# NIRGM_V3_E7.net
KiCad netlist of a schematic drawn in EAGLE
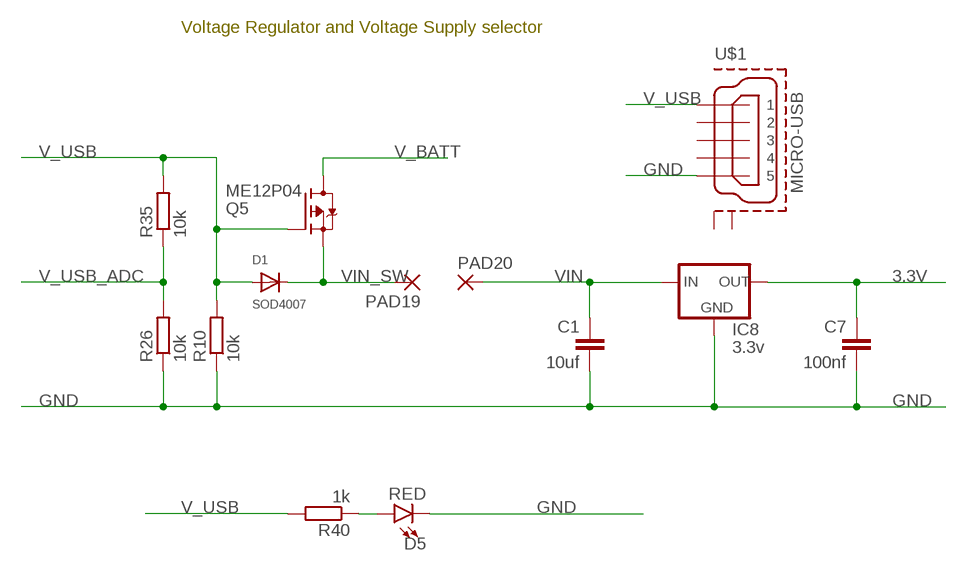
[diagram p0: schematic, sheet 1]
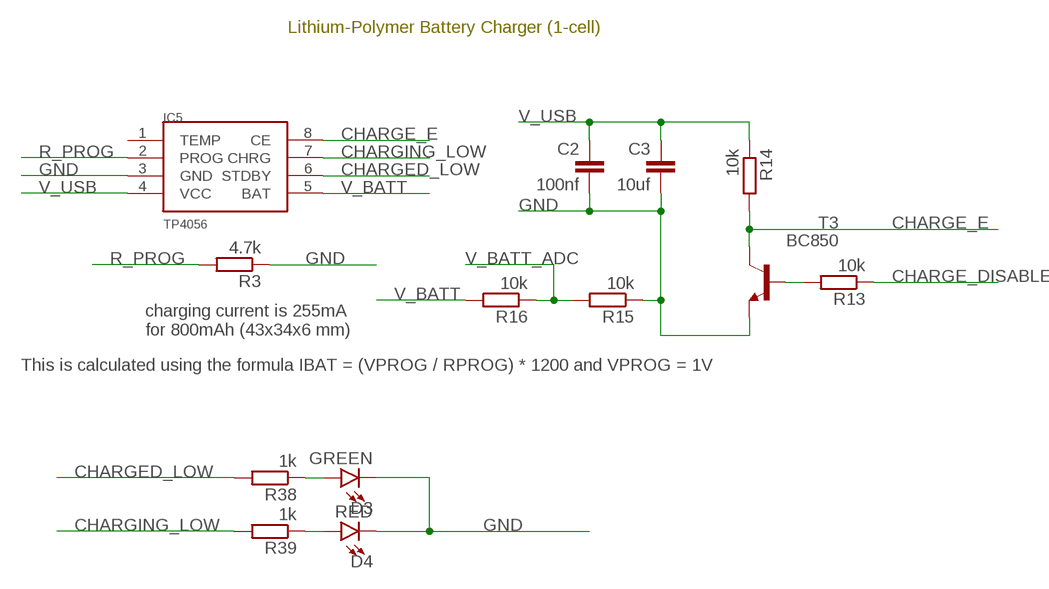
[diagram p1: schematic, sheet 2]
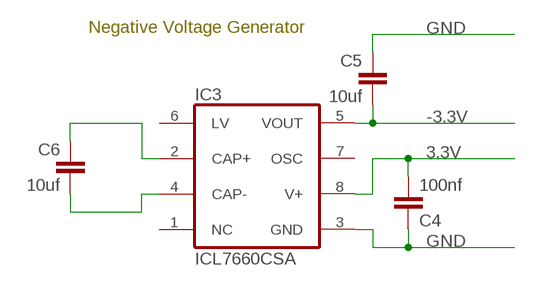
[diagram p2: schematic, sheet 3]
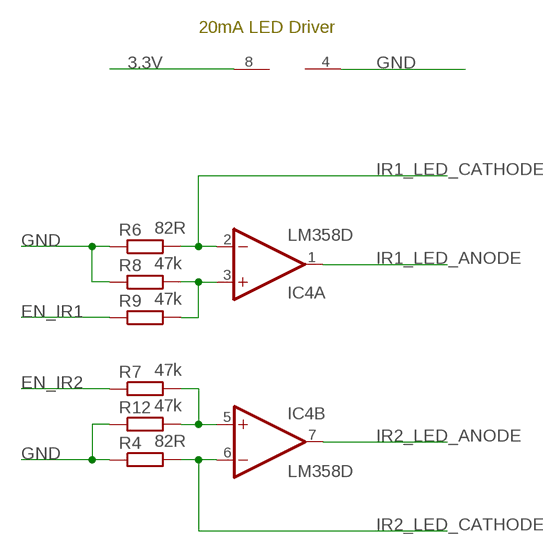
[diagram p3: schematic, sheet 4]
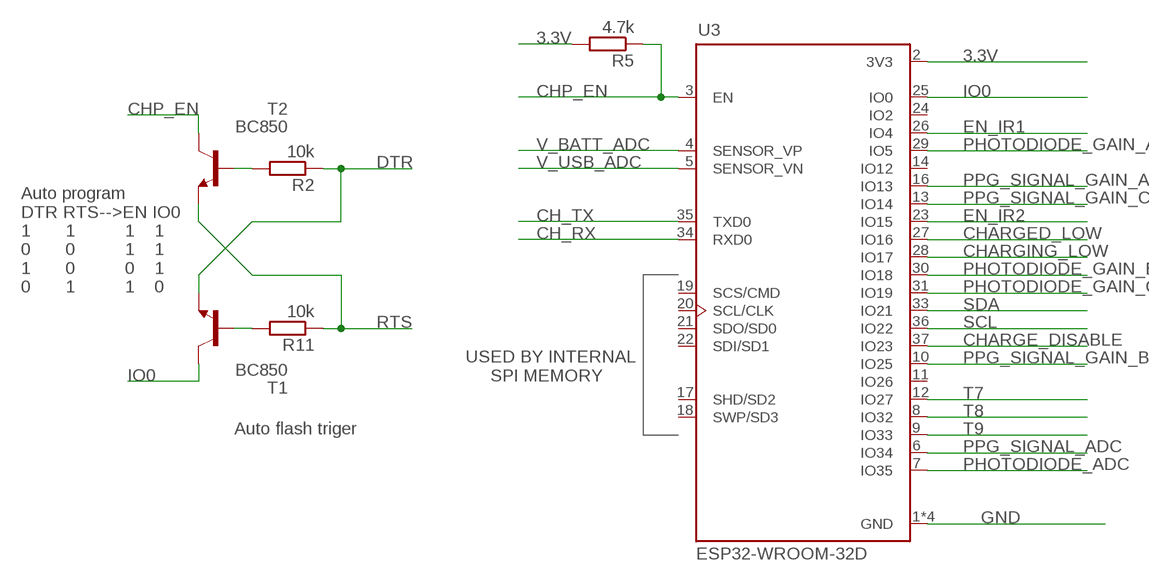
[diagram p4: schematic, sheet 5]
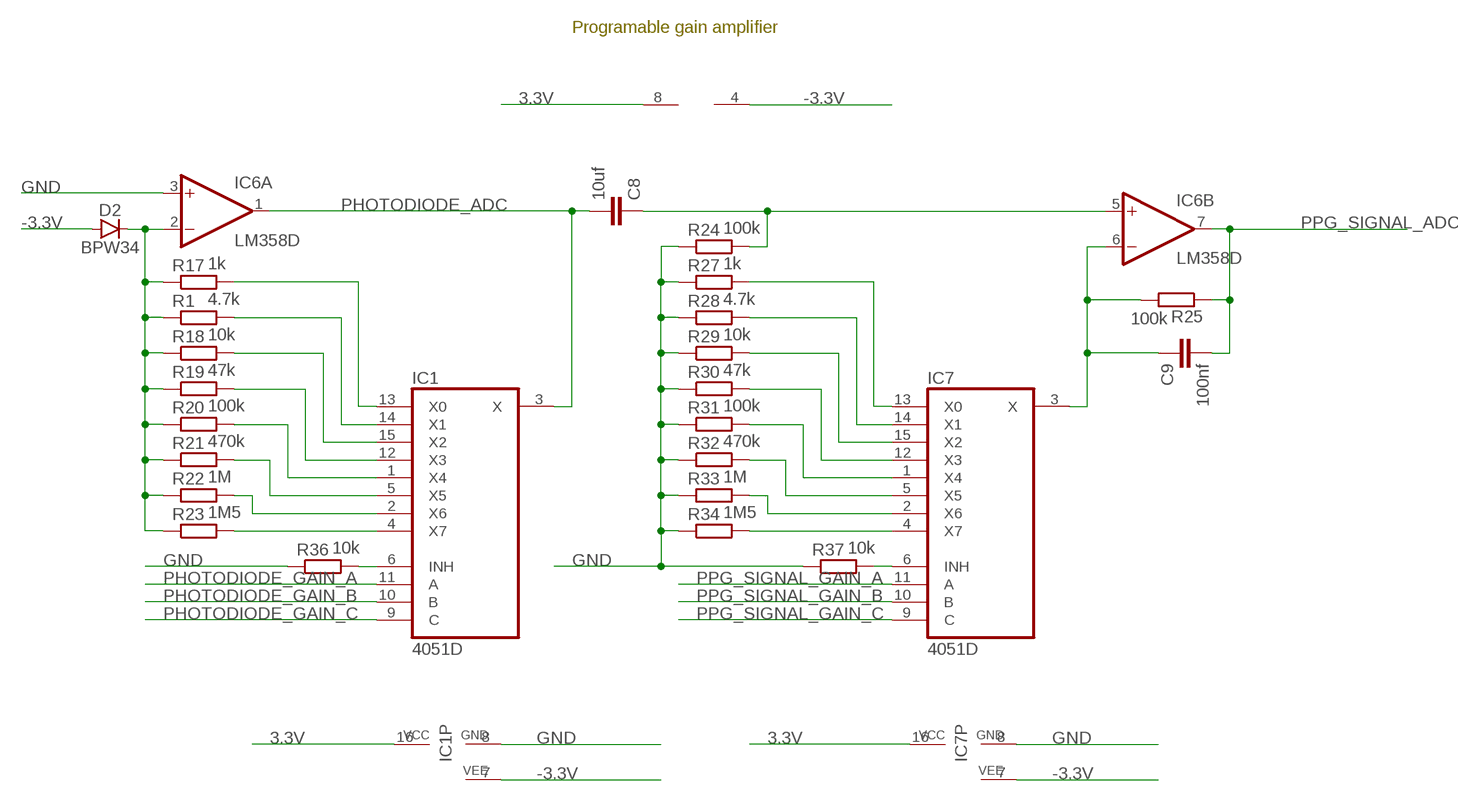
[diagram p5: schematic, sheet 6]
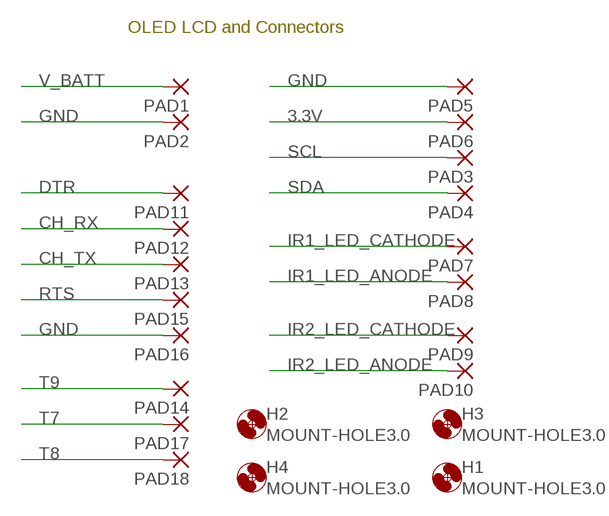
[diagram p6: schematic, sheet 7]

(export (version "E")
  (design (tool "Eeschema 10.0.6"))
  (components
    (comp (ref "IC4")
      (value "LM358D")
      (footprint "eagle-import:SO08")
      (libsource (lib "eagle-import") (part "LM358D"))
    )
    (comp (ref "R4")
      (value "82R")
      (footprint "eagle-import:R1206")
      (libsource (lib "eagle-import") (part "R-EU_R1206"))
    )
    (comp (ref "R6")
      (value "82R")
      (footprint "eagle-import:R1206")
      (libsource (lib "eagle-import") (part "R-EU_R1206"))
    )
    (comp (ref "R7")
      (value "47k")
      (footprint "eagle-import:R1206")
      (libsource (lib "eagle-import") (part "R-EU_R1206"))
    )
    (comp (ref "R8")
      (value "47k")
      (footprint "eagle-import:R1206")
      (libsource (lib "eagle-import") (part "R-EU_R1206"))
    )
    (comp (ref "R9")
      (value "47k")
      (footprint "eagle-import:R1206")
      (libsource (lib "eagle-import") (part "R-EU_R1206"))
    )
    (comp (ref "R12")
      (value "47k")
      (footprint "eagle-import:R1206")
      (libsource (lib "eagle-import") (part "R-EU_R1206"))
    )
    (comp (ref "C2")
      (value "100nf")
      (footprint "eagle-import:C1206K")
      (libsource (lib "eagle-import") (part "C-EUC1206K"))
    )
    (comp (ref "C3")
      (value "10uf")
      (footprint "eagle-import:C1206K")
      (libsource (lib "eagle-import") (part "C-EUC1206K"))
    )
    (comp (ref "D3")
      (value "GREEN")
      (footprint "eagle-import:LED-1206")
      (libsource (lib "eagle-import") (part "LED-GREEN1206"))
    )
    (comp (ref "D4")
      (value "RED")
      (footprint "eagle-import:LED-1206")
      (libsource (lib "eagle-import") (part "LED-GREEN1206"))
    )
    (comp (ref "IC5")
      (value "TP4056")
      (footprint "eagle-import:SOP-8")
      (libsource (lib "eagle-import") (part "TP4056"))
    )
    (comp (ref "R3")
      (value "4.7k")
      (footprint "eagle-import:R1206")
      (libsource (lib "eagle-import") (part "R-EU_R1206"))
    )
    (comp (ref "R13")
      (value "10k")
      (footprint "eagle-import:R1206")
      (libsource (lib "eagle-import") (part "R-EU_R1206"))
    )
    (comp (ref "R14")
      (value "10k")
      (footprint "eagle-import:R1206")
      (libsource (lib "eagle-import") (part "R-EU_R1206"))
    )
    (comp (ref "R15")
      (value "10k")
      (footprint "eagle-import:R1206")
      (libsource (lib "eagle-import") (part "R-EU_R1206"))
    )
    (comp (ref "R16")
      (value "10k")
      (footprint "eagle-import:R1206")
      (libsource (lib "eagle-import") (part "R-EU_R1206"))
    )
    (comp (ref "R38")
      (value "1k")
      (footprint "eagle-import:R1206")
      (libsource (lib "eagle-import") (part "R-EU_R1206"))
    )
    (comp (ref "R39")
      (value "1k")
      (footprint "eagle-import:R1206")
      (libsource (lib "eagle-import") (part "R-EU_R1206"))
    )
    (comp (ref "T3")
      (value "BC850")
      (footprint "eagle-import:SOT23")
      (libsource (lib "eagle-import") (part "BC850"))
    )
    (comp (ref "C8")
      (value "10uf")
      (footprint "eagle-import:C1206K")
      (libsource (lib "eagle-import") (part "C-EUC1206K"))
    )
    (comp (ref "C9")
      (value "100nf")
      (footprint "eagle-import:C1206K")
      (libsource (lib "eagle-import") (part "C-EUC1206K"))
    )
    (comp (ref "D2")
      (value "BPW34")
      (footprint "eagle-import:BPW34")
      (libsource (lib "eagle-import") (part "BPW34"))
    )
    (comp (ref "IC1")
      (value "4051D")
      (footprint "eagle-import:SO16")
      (libsource (lib "eagle-import") (part "4051D"))
    )
    (comp (ref "IC6")
      (value "LM358D")
      (footprint "eagle-import:SO08")
      (libsource (lib "eagle-import") (part "linear@1_LM358D"))
    )
    (comp (ref "IC7")
      (value "4051D")
      (footprint "eagle-import:SO16")
      (libsource (lib "eagle-import") (part "4051D"))
    )
    (comp (ref "R1")
      (value "4.7k")
      (footprint "eagle-import:R1206")
      (libsource (lib "eagle-import") (part "R-EU_R1206"))
    )
    (comp (ref "R17")
      (value "1k")
      (footprint "eagle-import:R1206")
      (libsource (lib "eagle-import") (part "R-EU_R1206"))
    )
    (comp (ref "R18")
      (value "10k")
      (footprint "eagle-import:R1206")
      (libsource (lib "eagle-import") (part "R-EU_R1206"))
    )
    (comp (ref "R19")
      (value "47k")
      (footprint "eagle-import:R1206")
      (libsource (lib "eagle-import") (part "R-EU_R1206"))
    )
    (comp (ref "R20")
      (value "100k")
      (footprint "eagle-import:R1206")
      (libsource (lib "eagle-import") (part "R-EU_R1206"))
    )
    (comp (ref "R21")
      (value "470k")
      (footprint "eagle-import:R1206")
      (libsource (lib "eagle-import") (part "R-EU_R1206"))
    )
    (comp (ref "R22")
      (value "1M")
      (footprint "eagle-import:R1206")
      (libsource (lib "eagle-import") (part "R-EU_R1206"))
    )
    (comp (ref "R23")
      (value "1M5")
      (footprint "eagle-import:R1206")
      (libsource (lib "eagle-import") (part "R-EU_R1206"))
    )
    (comp (ref "R24")
      (value "100k")
      (footprint "eagle-import:R1206")
      (libsource (lib "eagle-import") (part "R-EU_R1206"))
    )
    (comp (ref "R25")
      (value "100k")
      (footprint "eagle-import:R1206")
      (libsource (lib "eagle-import") (part "R-EU_R1206"))
    )
    (comp (ref "R27")
      (value "1k")
      (footprint "eagle-import:R1206")
      (libsource (lib "eagle-import") (part "R-EU_R1206"))
    )
    (comp (ref "R28")
      (value "4.7k")
      (footprint "eagle-import:R1206")
      (libsource (lib "eagle-import") (part "R-EU_R1206"))
    )
    (comp (ref "R29")
      (value "10k")
      (footprint "eagle-import:R1206")
      (libsource (lib "eagle-import") (part "R-EU_R1206"))
    )
    (comp (ref "R30")
      (value "47k")
      (footprint "eagle-import:R1206")
      (libsource (lib "eagle-import") (part "R-EU_R1206"))
    )
    (comp (ref "R31")
      (value "100k")
      (footprint "eagle-import:R1206")
      (libsource (lib "eagle-import") (part "R-EU_R1206"))
    )
    (comp (ref "R32")
      (value "470k")
      (footprint "eagle-import:R1206")
      (libsource (lib "eagle-import") (part "R-EU_R1206"))
    )
    (comp (ref "R33")
      (value "1M")
      (footprint "eagle-import:R1206")
      (libsource (lib "eagle-import") (part "R-EU_R1206"))
    )
    (comp (ref "R34")
      (value "1M5")
      (footprint "eagle-import:R1206")
      (libsource (lib "eagle-import") (part "R-EU_R1206"))
    )
    (comp (ref "R36")
      (value "10k")
      (footprint "eagle-import:R1206")
      (libsource (lib "eagle-import") (part "R-EU_R1206"))
    )
    (comp (ref "R37")
      (value "10k")
      (footprint "eagle-import:R1206")
      (libsource (lib "eagle-import") (part "R-EU_R1206"))
    )
    (comp (ref "H1")
      (value "MOUNT-HOLE3.0")
      (footprint "eagle-import:3,0")
      (libsource (lib "eagle-import") (part "MOUNT-HOLE3.0"))
    )
    (comp (ref "H2")
      (value "MOUNT-HOLE3.0")
      (footprint "eagle-import:3,0")
      (libsource (lib "eagle-import") (part "MOUNT-HOLE3.0"))
    )
    (comp (ref "H3")
      (value "MOUNT-HOLE3.0")
      (footprint "eagle-import:3,0")
      (libsource (lib "eagle-import") (part "MOUNT-HOLE3.0"))
    )
    (comp (ref "H4")
      (value "MOUNT-HOLE3.0")
      (footprint "eagle-import:3,0")
      (libsource (lib "eagle-import") (part "MOUNT-HOLE3.0"))
    )
    (comp (ref "PAD1")
      (value "WIREPADSMD5-2,5")
      (footprint "eagle-import:5-2,5")
      (libsource (lib "eagle-import") (part "WIREPADSMD5-2,5"))
    )
    (comp (ref "PAD2")
      (value "WIREPADSMD5-2,5")
      (footprint "eagle-import:5-2,5")
      (libsource (lib "eagle-import") (part "WIREPADSMD5-2,5"))
    )
    (comp (ref "PAD3")
      (value "SMD2")
      (footprint "eagle-import:SMD1,27-2,54")
      (libsource (lib "eagle-import") (part "SMD2"))
    )
    (comp (ref "PAD4")
      (value "SMD2")
      (footprint "eagle-import:SMD1,27-2,54")
      (libsource (lib "eagle-import") (part "SMD2"))
    )
    (comp (ref "PAD5")
      (value "SMD2")
      (footprint "eagle-import:SMD1,27-2,54")
      (libsource (lib "eagle-import") (part "SMD2"))
    )
    (comp (ref "PAD6")
      (value "SMD2")
      (footprint "eagle-import:SMD1,27-2,54")
      (libsource (lib "eagle-import") (part "SMD2"))
    )
    (comp (ref "PAD7")
      (value "SMD2")
      (footprint "eagle-import:SMD1,27-2,54")
      (libsource (lib "eagle-import") (part "SMD2"))
    )
    (comp (ref "PAD8")
      (value "SMD2")
      (footprint "eagle-import:SMD1,27-2,54")
      (libsource (lib "eagle-import") (part "SMD2"))
    )
    (comp (ref "PAD9")
      (value "SMD2")
      (footprint "eagle-import:SMD1,27-2,54")
      (libsource (lib "eagle-import") (part "SMD2"))
    )
    (comp (ref "PAD10")
      (value "SMD2")
      (footprint "eagle-import:SMD1,27-2,54")
      (libsource (lib "eagle-import") (part "SMD2"))
    )
    (comp (ref "PAD11")
      (value "SMD2")
      (footprint "eagle-import:SMD1,27-2,54")
      (libsource (lib "eagle-import") (part "SMD2"))
    )
    (comp (ref "PAD12")
      (value "SMD2")
      (footprint "eagle-import:SMD1,27-2,54")
      (libsource (lib "eagle-import") (part "SMD2"))
    )
    (comp (ref "PAD13")
      (value "SMD2")
      (footprint "eagle-import:SMD1,27-2,54")
      (libsource (lib "eagle-import") (part "SMD2"))
    )
    (comp (ref "PAD14")
      (value "SMD2")
      (footprint "eagle-import:SMD1,27-2,54")
      (libsource (lib "eagle-import") (part "SMD2"))
    )
    (comp (ref "PAD15")
      (value "SMD2")
      (footprint "eagle-import:SMD1,27-2,54")
      (libsource (lib "eagle-import") (part "SMD2"))
    )
    (comp (ref "PAD16")
      (value "SMD2")
      (footprint "eagle-import:SMD1,27-2,54")
      (libsource (lib "eagle-import") (part "SMD2"))
    )
    (comp (ref "PAD17")
      (value "SMD2")
      (footprint "eagle-import:SMD1,27-2,54")
      (libsource (lib "eagle-import") (part "SMD2"))
    )
    (comp (ref "PAD18")
      (value "SMD2")
      (footprint "eagle-import:SMD1,27-2,54")
      (libsource (lib "eagle-import") (part "SMD2"))
    )
    (comp (ref "C1")
      (value "10uf")
      (footprint "eagle-import:C1206K")
      (libsource (lib "eagle-import") (part "C-EUC1206K"))
    )
    (comp (ref "C7")
      (value "100nf")
      (footprint "eagle-import:C1206K")
      (libsource (lib "eagle-import") (part "C-EUC1206K"))
    )
    (comp (ref "D1")
      (value "SOD4007")
      (footprint "eagle-import:SOD-123FL")
      (libsource (lib "eagle-import") (part "DIODE_SOD-123FL"))
    )
    (comp (ref "D5")
      (value "RED")
      (footprint "eagle-import:LED-1206")
      (libsource (lib "eagle-import") (part "LED-GREEN1206"))
    )
    (comp (ref "IC8")
      (value "3.3v")
      (footprint "eagle-import:TO252")
      (libsource (lib "eagle-import") (part "LM1117TO252"))
    )
    (comp (ref "PAD19")
      (value "SMD2")
      (footprint "eagle-import:SMD1,27-2,54")
      (libsource (lib "eagle-import") (part "SMD2"))
    )
    (comp (ref "PAD20")
      (value "SMD2")
      (footprint "eagle-import:SMD1,27-2,54")
      (libsource (lib "eagle-import") (part "SMD2"))
    )
    (comp (ref "Q5")
      (value "ME12P04")
      (footprint "eagle-import:TO252")
      (libsource (lib "eagle-import") (part "FDD4141TO252"))
    )
    (comp (ref "R10")
      (value "10k")
      (footprint "eagle-import:R1206")
      (libsource (lib "eagle-import") (part "R-EU_R1206"))
    )
    (comp (ref "R26")
      (value "10k")
      (footprint "eagle-import:R1206")
      (libsource (lib "eagle-import") (part "R-EU_R1206"))
    )
    (comp (ref "R35")
      (value "10k")
      (footprint "eagle-import:R1206")
      (libsource (lib "eagle-import") (part "R-EU_R1206"))
    )
    (comp (ref "R40")
      (value "1k")
      (footprint "eagle-import:R1206")
      (libsource (lib "eagle-import") (part "R-EU_R1206"))
    )
    (comp (ref "U$1")
      (value "MICRO-USB")
      (footprint "eagle-import:47589-0001")
      (libsource (lib "eagle-import") (part "MICRO-USB-RECEPTACLE47589-0001"))
    )
    (comp (ref "C4")
      (value "100nf")
      (footprint "eagle-import:C1206K")
      (libsource (lib "eagle-import") (part "C-EUC1206K"))
    )
    (comp (ref "C5")
      (value "10uf")
      (footprint "eagle-import:C1206K")
      (libsource (lib "eagle-import") (part "C-EUC1206K"))
    )
    (comp (ref "C6")
      (value "10uf")
      (footprint "eagle-import:C1206K")
      (libsource (lib "eagle-import") (part "C-EUC1206K"))
    )
    (comp (ref "IC3")
      (value "ICL7660CSA")
      (footprint "eagle-import:SO08")
      (fields (field (name "MF") "MAXIM"))
      (libsource (lib "eagle-import") (part "ICL7660CSA"))
    )
    (comp (ref "R2")
      (value "10k")
      (footprint "eagle-import:R1206")
      (libsource (lib "eagle-import") (part "R-EU_R1206"))
    )
    (comp (ref "R5")
      (value "4.7k")
      (footprint "eagle-import:R1206")
      (libsource (lib "eagle-import") (part "R-EU_R1206"))
    )
    (comp (ref "R11")
      (value "10k")
      (footprint "eagle-import:R1206")
      (libsource (lib "eagle-import") (part "R-EU_R1206"))
    )
    (comp (ref "T1")
      (value "BC850")
      (footprint "eagle-import:SOT23")
      (libsource (lib "eagle-import") (part "BC850"))
    )
    (comp (ref "T2")
      (value "BC850")
      (footprint "eagle-import:SOT23")
      (libsource (lib "eagle-import") (part "BC850"))
    )
    (comp (ref "U3")
      (value "ESP32-WROOM-32D")
      (footprint "eagle-import:MODULE_ESP32-WROOM-32D")
      (fields (field (name "MF") "Espressif Systems"))
      (libsource (lib "eagle-import") (part "ESP32-WROOM-32D"))
    )
  )
  (nets
    (net (code "1") (name "-3.3V") (class "Default")
      (node (ref "C5") (pin "2") (pinfunction "2_2") (pintype "passive"))
      (node (ref "D2") (pin "P$1") (pinfunction "A_P$1") (pintype "passive"))
      (node (ref "IC1") (pin "7") (pinfunction "VEE_7") (pintype "power_in"))
      (node (ref "IC3") (pin "5") (pinfunction "VOUT_5") (pintype "output"))
      (node (ref "IC6") (pin "4") (pinfunction "V-_4") (pintype "power_in"))
      (node (ref "IC7") (pin "7") (pinfunction "VEE_7") (pintype "power_in"))
    )
    (net (code "2") (name "3.3V") (class "Default")
      (node (ref "C4") (pin "2") (pinfunction "2_2") (pintype "passive"))
      (node (ref "C7") (pin "1") (pinfunction "1_1") (pintype "passive"))
      (node (ref "IC1") (pin "16") (pinfunction "VCC_16") (pintype "power_in"))
      (node (ref "IC3") (pin "8") (pinfunction "V+_8") (pintype "power_in"))
      (node (ref "IC4") (pin "8") (pinfunction "V+_8") (pintype "power_in"))
      (node (ref "IC6") (pin "8") (pinfunction "V+_8") (pintype "power_in"))
      (node (ref "IC7") (pin "16") (pinfunction "VCC_16") (pintype "power_in"))
      (node (ref "IC8") (pin "3") (pinfunction "OUT_3") (pintype "passive"))
      (node (ref "PAD6") (pin "1") (pinfunction "P_1") (pintype "passive"))
      (node (ref "R5") (pin "2") (pinfunction "2_2") (pintype "passive"))
      (node (ref "U3") (pin "2") (pinfunction "3V3_2") (pintype "power_in"))
    )
    (net (code "3") (name "CHARGED_LOW") (class "Default")
      (node (ref "IC5") (pin "6") (pinfunction "STDBY_6") (pintype "bidirectional"))
      (node (ref "R38") (pin "2") (pinfunction "2_2") (pintype "passive"))
      (node (ref "U3") (pin "27") (pinfunction "IO16_27") (pintype "bidirectional"))
    )
    (net (code "4") (name "CHARGE_DISABLE") (class "Default")
      (node (ref "R13") (pin "1") (pinfunction "1_1") (pintype "passive"))
      (node (ref "U3") (pin "37") (pinfunction "IO23_37") (pintype "bidirectional"))
    )
    (net (code "5") (name "CHARGE_E") (class "Default")
      (node (ref "IC5") (pin "8") (pinfunction "CE_8") (pintype "bidirectional"))
      (node (ref "R14") (pin "2") (pinfunction "2_2") (pintype "passive"))
      (node (ref "T3") (pin "3") (pinfunction "C_3") (pintype "passive"))
    )
    (net (code "6") (name "CHARGING_LOW") (class "Default")
      (node (ref "IC5") (pin "7") (pinfunction "CHRG_7") (pintype "bidirectional"))
      (node (ref "R39") (pin "2") (pinfunction "2_2") (pintype "passive"))
      (node (ref "U3") (pin "28") (pinfunction "IO17_28") (pintype "bidirectional"))
    )
    (net (code "7") (name "CHP_EN") (class "Default")
      (node (ref "R5") (pin "1") (pinfunction "1_1") (pintype "passive"))
      (node (ref "T2") (pin "3") (pinfunction "C_3") (pintype "passive"))
      (node (ref "U3") (pin "3") (pinfunction "EN_3") (pintype "input"))
    )
    (net (code "8") (name "CH_RX") (class "Default")
      (node (ref "PAD12") (pin "1") (pinfunction "P_1") (pintype "passive"))
      (node (ref "U3") (pin "34") (pinfunction "RXD0_34") (pintype "bidirectional"))
    )
    (net (code "9") (name "CH_TX") (class "Default")
      (node (ref "PAD13") (pin "1") (pinfunction "P_1") (pintype "passive"))
      (node (ref "U3") (pin "35") (pinfunction "TXD0_35") (pintype "bidirectional"))
    )
    (net (code "10") (name "DTR") (class "Default")
      (node (ref "PAD11") (pin "1") (pinfunction "P_1") (pintype "passive"))
      (node (ref "R2") (pin "1") (pinfunction "1_1") (pintype "passive"))
      (node (ref "T1") (pin "2") (pinfunction "E_2") (pintype "passive"))
    )
    (net (code "11") (name "EN_IR1") (class "Default")
      (node (ref "R9") (pin "1") (pinfunction "1_1") (pintype "passive"))
      (node (ref "U3") (pin "26") (pinfunction "IO4_26") (pintype "bidirectional"))
    )
    (net (code "12") (name "EN_IR2") (class "Default")
      (node (ref "R7") (pin "1") (pinfunction "1_1") (pintype "passive"))
      (node (ref "U3") (pin "23") (pinfunction "IO15_23") (pintype "bidirectional"))
    )
    (net (code "13") (name "GND") (class "Default")
      (node (ref "C1") (pin "2") (pinfunction "2_2") (pintype "passive"))
      (node (ref "C2") (pin "2") (pinfunction "2_2") (pintype "passive"))
      (node (ref "C3") (pin "2") (pinfunction "2_2") (pintype "passive"))
      (node (ref "C4") (pin "1") (pinfunction "1_1") (pintype "passive"))
      (node (ref "C5") (pin "1") (pinfunction "1_1") (pintype "passive"))
      (node (ref "C7") (pin "2") (pinfunction "2_2") (pintype "passive"))
      (node (ref "D3") (pin "C") (pinfunction "C_C") (pintype "passive"))
      (node (ref "D4") (pin "C") (pinfunction "C_C") (pintype "passive"))
      (node (ref "D5") (pin "C") (pinfunction "C_C") (pintype "passive"))
      (node (ref "IC1") (pin "8") (pinfunction "GND_8") (pintype "power_in"))
      (node (ref "IC3") (pin "3") (pinfunction "GND_3") (pintype "power_in"))
      (node (ref "IC4") (pin "4") (pinfunction "V-_4") (pintype "power_in"))
      (node (ref "IC5") (pin "3") (pinfunction "GND_3") (pintype "bidirectional"))
      (node (ref "IC6") (pin "3") (pinfunction "+IN_3") (pintype "input"))
      (node (ref "IC7") (pin "8") (pinfunction "GND_8") (pintype "power_in"))
      (node (ref "IC8") (pin "1") (pinfunction "GND_1") (pintype "input"))
      (node (ref "PAD16") (pin "1") (pinfunction "P_1") (pintype "passive"))
      (node (ref "PAD2") (pin "1") (pinfunction "P_1") (pintype "passive"))
      (node (ref "PAD5") (pin "1") (pinfunction "P_1") (pintype "passive"))
      (node (ref "R10") (pin "1") (pinfunction "1_1") (pintype "passive"))
      (node (ref "R12") (pin "1") (pinfunction "1_1") (pintype "passive"))
      (node (ref "R15") (pin "1") (pinfunction "1_1") (pintype "passive"))
      (node (ref "R24") (pin "1") (pinfunction "1_1") (pintype "passive"))
      (node (ref "R26") (pin "1") (pinfunction "1_1") (pintype "passive"))
      (node (ref "R27") (pin "1") (pinfunction "1_1") (pintype "passive"))
      (node (ref "R28") (pin "1") (pinfunction "1_1") (pintype "passive"))
      (node (ref "R29") (pin "1") (pinfunction "1_1") (pintype "passive"))
      (node (ref "R3") (pin "1") (pinfunction "1_1") (pintype "passive"))
      (node (ref "R30") (pin "1") (pinfunction "1_1") (pintype "passive"))
      (node (ref "R31") (pin "1") (pinfunction "1_1") (pintype "passive"))
      (node (ref "R32") (pin "1") (pinfunction "1_1") (pintype "passive"))
      (node (ref "R33") (pin "1") (pinfunction "1_1") (pintype "passive"))
      (node (ref "R34") (pin "1") (pinfunction "1_1") (pintype "passive"))
      (node (ref "R36") (pin "1") (pinfunction "1_1") (pintype "passive"))
      (node (ref "R37") (pin "1") (pinfunction "1_1") (pintype "passive"))
      (node (ref "R4") (pin "1") (pinfunction "1_1") (pintype "passive"))
      (node (ref "R6") (pin "1") (pinfunction "1_1") (pintype "passive"))
      (node (ref "R8") (pin "1") (pinfunction "1_1") (pintype "passive"))
      (node (ref "T3") (pin "2") (pinfunction "E_2") (pintype "passive"))
      (node (ref "U$1") (pin "5") (pinfunction "5_5") (pintype "input"))
      (node (ref "U3") (pin "1") (pinfunction "GND_1") (pintype "power_in"))
      (node (ref "U3") (pin "15") (pinfunction "GND_15") (pintype "power_in"))
      (node (ref "U3") (pin "38") (pinfunction "GND_38") (pintype "power_in"))
      (node (ref "U3") (pin "39") (pinfunction "GND_39") (pintype "power_in"))
    )
    (net (code "14") (name "IO0") (class "Default")
      (node (ref "T1") (pin "3") (pinfunction "C_3") (pintype "passive"))
      (node (ref "U3") (pin "25") (pinfunction "IO0_25") (pintype "bidirectional"))
    )
    (net (code "15") (name "IR1_LED_ANODE") (class "Default")
      (node (ref "IC4") (pin "1") (pinfunction "OUT_1") (pintype "output"))
      (node (ref "PAD8") (pin "1") (pinfunction "P_1") (pintype "passive"))
    )
    (net (code "16") (name "IR1_LED_CATHODE") (class "Default")
      (node (ref "IC4") (pin "2") (pinfunction "-IN_2") (pintype "input"))
      (node (ref "PAD7") (pin "1") (pinfunction "P_1") (pintype "passive"))
      (node (ref "R6") (pin "2") (pinfunction "2_2") (pintype "passive"))
    )
    (net (code "17") (name "IR2_LED_ANODE") (class "Default")
      (node (ref "IC4") (pin "7") (pinfunction "OUT_7") (pintype "output"))
      (node (ref "PAD10") (pin "1") (pinfunction "P_1") (pintype "passive"))
    )
    (net (code "18") (name "IR2_LED_CATHODE") (class "Default")
      (node (ref "IC4") (pin "6") (pinfunction "-IN_6") (pintype "input"))
      (node (ref "PAD9") (pin "1") (pinfunction "P_1") (pintype "passive"))
      (node (ref "R4") (pin "2") (pinfunction "2_2") (pintype "passive"))
    )
    (net (code "19") (name "Net-(D2-C)") (class "Default")
      (node (ref "D2") (pin "P$2") (pinfunction "C_P$2") (pintype "passive"))
      (node (ref "IC6") (pin "2") (pinfunction "-IN_2") (pintype "input"))
      (node (ref "R1") (pin "1") (pinfunction "1_1") (pintype "passive"))
      (node (ref "R17") (pin "1") (pinfunction "1_1") (pintype "passive"))
      (node (ref "R18") (pin "1") (pinfunction "1_1") (pintype "passive"))
      (node (ref "R19") (pin "1") (pinfunction "1_1") (pintype "passive"))
      (node (ref "R20") (pin "1") (pinfunction "1_1") (pintype "passive"))
      (node (ref "R21") (pin "1") (pinfunction "1_1") (pintype "passive"))
      (node (ref "R22") (pin "1") (pinfunction "1_1") (pintype "passive"))
      (node (ref "R23") (pin "1") (pinfunction "1_1") (pintype "passive"))
    )
    (net (code "20") (name "Net-(D3-PadA)") (class "Default")
      (node (ref "D3") (pin "A") (pinfunction "A_A") (pintype "passive"))
      (node (ref "R38") (pin "1") (pinfunction "1_1") (pintype "passive"))
    )
    (net (code "21") (name "Net-(D4-PadA)") (class "Default")
      (node (ref "D4") (pin "A") (pinfunction "A_A") (pintype "passive"))
      (node (ref "R39") (pin "1") (pinfunction "1_1") (pintype "passive"))
    )
    (net (code "22") (name "Net-(D5-PadA)") (class "Default")
      (node (ref "D5") (pin "A") (pinfunction "A_A") (pintype "passive"))
      (node (ref "R40") (pin "1") (pinfunction "1_1") (pintype "passive"))
    )
    (net (code "23") (name "Net-(IC1A-INH)") (class "Default")
      (node (ref "IC1") (pin "6") (pinfunction "INH_6") (pintype "input"))
      (node (ref "R36") (pin "2") (pinfunction "2_2") (pintype "passive"))
    )
    (net (code "24") (name "Net-(IC1A-X0)") (class "Default")
      (node (ref "IC1") (pin "13") (pinfunction "X0_13") (pintype "bidirectional"))
      (node (ref "R17") (pin "2") (pinfunction "2_2") (pintype "passive"))
    )
    (net (code "25") (name "Net-(IC1A-X1)") (class "Default")
      (node (ref "IC1") (pin "14") (pinfunction "X1_14") (pintype "bidirectional"))
      (node (ref "R1") (pin "2") (pinfunction "2_2") (pintype "passive"))
    )
    (net (code "26") (name "Net-(IC1A-X2)") (class "Default")
      (node (ref "IC1") (pin "15") (pinfunction "X2_15") (pintype "bidirectional"))
      (node (ref "R18") (pin "2") (pinfunction "2_2") (pintype "passive"))
    )
    (net (code "27") (name "Net-(IC1A-X3)") (class "Default")
      (node (ref "IC1") (pin "12") (pinfunction "X3_12") (pintype "bidirectional"))
      (node (ref "R19") (pin "2") (pinfunction "2_2") (pintype "passive"))
    )
    (net (code "28") (name "Net-(IC1A-X4)") (class "Default")
      (node (ref "IC1") (pin "1") (pinfunction "X4_1") (pintype "bidirectional"))
      (node (ref "R20") (pin "2") (pinfunction "2_2") (pintype "passive"))
    )
    (net (code "29") (name "Net-(IC1A-X5)") (class "Default")
      (node (ref "IC1") (pin "5") (pinfunction "X5_5") (pintype "bidirectional"))
      (node (ref "R21") (pin "2") (pinfunction "2_2") (pintype "passive"))
    )
    (net (code "30") (name "Net-(IC1A-X6)") (class "Default")
      (node (ref "IC1") (pin "2") (pinfunction "X6_2") (pintype "bidirectional"))
      (node (ref "R22") (pin "2") (pinfunction "2_2") (pintype "passive"))
    )
    (net (code "31") (name "Net-(IC1A-X7)") (class "Default")
      (node (ref "IC1") (pin "4") (pinfunction "X7_4") (pintype "bidirectional"))
      (node (ref "R23") (pin "2") (pinfunction "2_2") (pintype "passive"))
    )
    (net (code "32") (name "Net-(IC3-CAP+)") (class "Default")
      (node (ref "C6") (pin "1") (pinfunction "1_1") (pintype "passive"))
      (node (ref "IC3") (pin "2") (pinfunction "CAP+_2") (pintype "passive"))
    )
    (net (code "33") (name "Net-(IC3-CAP-)") (class "Default")
      (node (ref "C6") (pin "2") (pinfunction "2_2") (pintype "passive"))
      (node (ref "IC3") (pin "4") (pinfunction "CAP-_4") (pintype "passive"))
    )
    (net (code "34") (name "Net-(IC4A-+IN)") (class "Default")
      (node (ref "IC4") (pin "3") (pinfunction "+IN_3") (pintype "input"))
      (node (ref "R8") (pin "2") (pinfunction "2_2") (pintype "passive"))
      (node (ref "R9") (pin "2") (pinfunction "2_2") (pintype "passive"))
    )
    (net (code "35") (name "Net-(IC4B-+IN)") (class "Default")
      (node (ref "IC4") (pin "5") (pinfunction "+IN_5") (pintype "input"))
      (node (ref "R12") (pin "2") (pinfunction "2_2") (pintype "passive"))
      (node (ref "R7") (pin "2") (pinfunction "2_2") (pintype "passive"))
    )
    (net (code "36") (name "Net-(IC6B-+IN)") (class "Default")
      (node (ref "C8") (pin "1") (pinfunction "1_1") (pintype "passive"))
      (node (ref "IC6") (pin "5") (pinfunction "+IN_5") (pintype "input"))
      (node (ref "R24") (pin "2") (pinfunction "2_2") (pintype "passive"))
    )
    (net (code "37") (name "Net-(IC6B--IN)") (class "Default")
      (node (ref "C9") (pin "1") (pinfunction "1_1") (pintype "passive"))
      (node (ref "IC6") (pin "6") (pinfunction "-IN_6") (pintype "input"))
      (node (ref "IC7") (pin "3") (pinfunction "X_3") (pintype "bidirectional"))
      (node (ref "R25") (pin "2") (pinfunction "2_2") (pintype "passive"))
    )
    (net (code "38") (name "Net-(IC7A-INH)") (class "Default")
      (node (ref "IC7") (pin "6") (pinfunction "INH_6") (pintype "input"))
      (node (ref "R37") (pin "2") (pinfunction "2_2") (pintype "passive"))
    )
    (net (code "39") (name "Net-(IC7A-X0)") (class "Default")
      (node (ref "IC7") (pin "13") (pinfunction "X0_13") (pintype "bidirectional"))
      (node (ref "R27") (pin "2") (pinfunction "2_2") (pintype "passive"))
    )
    (net (code "40") (name "Net-(IC7A-X1)") (class "Default")
      (node (ref "IC7") (pin "14") (pinfunction "X1_14") (pintype "bidirectional"))
      (node (ref "R28") (pin "2") (pinfunction "2_2") (pintype "passive"))
    )
    (net (code "41") (name "Net-(IC7A-X2)") (class "Default")
      (node (ref "IC7") (pin "15") (pinfunction "X2_15") (pintype "bidirectional"))
      (node (ref "R29") (pin "2") (pinfunction "2_2") (pintype "passive"))
    )
    (net (code "42") (name "Net-(IC7A-X3)") (class "Default")
      (node (ref "IC7") (pin "12") (pinfunction "X3_12") (pintype "bidirectional"))
      (node (ref "R30") (pin "2") (pinfunction "2_2") (pintype "passive"))
    )
    (net (code "43") (name "Net-(IC7A-X4)") (class "Default")
      (node (ref "IC7") (pin "1") (pinfunction "X4_1") (pintype "bidirectional"))
      (node (ref "R31") (pin "2") (pinfunction "2_2") (pintype "passive"))
    )
    (net (code "44") (name "Net-(IC7A-X5)") (class "Default")
      (node (ref "IC7") (pin "5") (pinfunction "X5_5") (pintype "bidirectional"))
      (node (ref "R32") (pin "2") (pinfunction "2_2") (pintype "passive"))
    )
    (net (code "45") (name "Net-(IC7A-X6)") (class "Default")
      (node (ref "IC7") (pin "2") (pinfunction "X6_2") (pintype "bidirectional"))
      (node (ref "R33") (pin "2") (pinfunction "2_2") (pintype "passive"))
    )
    (net (code "46") (name "Net-(IC7A-X7)") (class "Default")
      (node (ref "IC7") (pin "4") (pinfunction "X7_4") (pintype "bidirectional"))
      (node (ref "R34") (pin "2") (pinfunction "2_2") (pintype "passive"))
    )
    (net (code "47") (name "Net-(T1-B)") (class "Default")
      (node (ref "R11") (pin "2") (pinfunction "2_2") (pintype "passive"))
      (node (ref "T1") (pin "1") (pinfunction "B_1") (pintype "passive"))
    )
    (net (code "48") (name "Net-(T2-B)") (class "Default")
      (node (ref "R2") (pin "2") (pinfunction "2_2") (pintype "passive"))
      (node (ref "T2") (pin "1") (pinfunction "B_1") (pintype "passive"))
    )
    (net (code "49") (name "Net-(T3-B)") (class "Default")
      (node (ref "R13") (pin "2") (pinfunction "2_2") (pintype "passive"))
      (node (ref "T3") (pin "1") (pinfunction "B_1") (pintype "passive"))
    )
    (net (code "50") (name "PHOTODIODE_ADC") (class "Default")
      (node (ref "C8") (pin "2") (pinfunction "2_2") (pintype "passive"))
      (node (ref "IC1") (pin "3") (pinfunction "X_3") (pintype "bidirectional"))
      (node (ref "IC6") (pin "1") (pinfunction "OUT_1") (pintype "output"))
      (node (ref "U3") (pin "7") (pinfunction "IO35_7") (pintype "bidirectional"))
    )
    (net (code "51") (name "PHOTODIODE_GAIN_A") (class "Default")
      (node (ref "IC1") (pin "11") (pinfunction "A_11") (pintype "input"))
      (node (ref "U3") (pin "29") (pinfunction "IO5_29") (pintype "bidirectional"))
    )
    (net (code "52") (name "PHOTODIODE_GAIN_B") (class "Default")
      (node (ref "IC1") (pin "10") (pinfunction "B_10") (pintype "input"))
      (node (ref "U3") (pin "30") (pinfunction "IO18_30") (pintype "bidirectional"))
    )
    (net (code "53") (name "PHOTODIODE_GAIN_C") (class "Default")
      (node (ref "IC1") (pin "9") (pinfunction "C_9") (pintype "input"))
      (node (ref "U3") (pin "31") (pinfunction "IO19_31") (pintype "bidirectional"))
    )
    (net (code "54") (name "PPG_SIGNAL_ADC") (class "Default")
      (node (ref "C9") (pin "2") (pinfunction "2_2") (pintype "passive"))
      (node (ref "IC6") (pin "7") (pinfunction "OUT_7") (pintype "output"))
      (node (ref "R25") (pin "1") (pinfunction "1_1") (pintype "passive"))
      (node (ref "U3") (pin "6") (pinfunction "IO34_6") (pintype "bidirectional"))
    )
    (net (code "55") (name "PPG_SIGNAL_GAIN_A") (class "Default")
      (node (ref "IC7") (pin "11") (pinfunction "A_11") (pintype "input"))
      (node (ref "U3") (pin "16") (pinfunction "IO13_16") (pintype "bidirectional"))
    )
    (net (code "56") (name "PPG_SIGNAL_GAIN_B") (class "Default")
      (node (ref "IC7") (pin "10") (pinfunction "B_10") (pintype "input"))
      (node (ref "U3") (pin "10") (pinfunction "IO25_10") (pintype "bidirectional"))
    )
    (net (code "57") (name "PPG_SIGNAL_GAIN_C") (class "Default")
      (node (ref "IC7") (pin "9") (pinfunction "C_9") (pintype "input"))
      (node (ref "U3") (pin "13") (pinfunction "IO14_13") (pintype "bidirectional"))
    )
    (net (code "58") (name "RTS") (class "Default")
      (node (ref "PAD15") (pin "1") (pinfunction "P_1") (pintype "passive"))
      (node (ref "R11") (pin "1") (pinfunction "1_1") (pintype "passive"))
      (node (ref "T2") (pin "2") (pinfunction "E_2") (pintype "passive"))
    )
    (net (code "59") (name "R_PROG") (class "Default")
      (node (ref "IC5") (pin "2") (pinfunction "PROG_2") (pintype "bidirectional"))
      (node (ref "R3") (pin "2") (pinfunction "2_2") (pintype "passive"))
    )
    (net (code "60") (name "SCL") (class "Default")
      (node (ref "PAD3") (pin "1") (pinfunction "P_1") (pintype "passive"))
      (node (ref "U3") (pin "36") (pinfunction "IO22_36") (pintype "bidirectional"))
    )
    (net (code "61") (name "SDA") (class "Default")
      (node (ref "PAD4") (pin "1") (pinfunction "P_1") (pintype "passive"))
      (node (ref "U3") (pin "33") (pinfunction "IO21_33") (pintype "bidirectional"))
    )
    (net (code "62") (name "T7") (class "Default")
      (node (ref "PAD17") (pin "1") (pinfunction "P_1") (pintype "passive"))
      (node (ref "U3") (pin "12") (pinfunction "IO27_12") (pintype "bidirectional"))
    )
    (net (code "63") (name "T8") (class "Default")
      (node (ref "PAD18") (pin "1") (pinfunction "P_1") (pintype "passive"))
      (node (ref "U3") (pin "8") (pinfunction "IO32_8") (pintype "bidirectional"))
    )
    (net (code "64") (name "T9") (class "Default")
      (node (ref "PAD14") (pin "1") (pinfunction "P_1") (pintype "passive"))
      (node (ref "U3") (pin "9") (pinfunction "IO33_9") (pintype "bidirectional"))
    )
    (net (code "65") (name "VIN") (class "Default")
      (node (ref "C1") (pin "1") (pinfunction "1_1") (pintype "passive"))
      (node (ref "IC8") (pin "2") (pinfunction "IN_2") (pintype "input"))
      (node (ref "PAD20") (pin "1") (pinfunction "P_1") (pintype "passive"))
    )
    (net (code "66") (name "VIN_SW") (class "Default")
      (node (ref "D1") (pin "C") (pinfunction "C_C") (pintype "passive"))
      (node (ref "PAD19") (pin "1") (pinfunction "P_1") (pintype "passive"))
      (node (ref "Q5") (pin "2") (pinfunction "S_2") (pintype "passive"))
    )
    (net (code "67") (name "V_BATT") (class "Default")
      (node (ref "IC5") (pin "5") (pinfunction "BAT_5") (pintype "bidirectional"))
      (node (ref "PAD1") (pin "1") (pinfunction "P_1") (pintype "passive"))
      (node (ref "Q5") (pin "3") (pinfunction "D_3") (pintype "passive"))
      (node (ref "R16") (pin "2") (pinfunction "2_2") (pintype "passive"))
    )
    (net (code "68") (name "V_BATT_ADC") (class "Default")
      (node (ref "R15") (pin "2") (pinfunction "2_2") (pintype "passive"))
      (node (ref "R16") (pin "1") (pinfunction "1_1") (pintype "passive"))
      (node (ref "U3") (pin "4") (pinfunction "SENSOR_VP_4") (pintype "input"))
    )
    (net (code "69") (name "V_USB") (class "Default")
      (node (ref "C2") (pin "1") (pinfunction "1_1") (pintype "passive"))
      (node (ref "C3") (pin "1") (pinfunction "1_1") (pintype "passive"))
      (node (ref "D1") (pin "A") (pinfunction "A_A") (pintype "passive"))
      (node (ref "IC5") (pin "4") (pinfunction "VCC_4") (pintype "bidirectional"))
      (node (ref "Q5") (pin "1") (pinfunction "G_1") (pintype "passive"))
      (node (ref "R10") (pin "2") (pinfunction "2_2") (pintype "passive"))
      (node (ref "R14") (pin "1") (pinfunction "1_1") (pintype "passive"))
      (node (ref "R35") (pin "2") (pinfunction "2_2") (pintype "passive"))
      (node (ref "R40") (pin "2") (pinfunction "2_2") (pintype "passive"))
      (node (ref "U$1") (pin "1") (pinfunction "1_1") (pintype "input"))
    )
    (net (code "70") (name "V_USB_ADC") (class "Default")
      (node (ref "R26") (pin "2") (pinfunction "2_2") (pintype "passive"))
      (node (ref "R35") (pin "1") (pinfunction "1_1") (pintype "passive"))
      (node (ref "U3") (pin "5") (pinfunction "SENSOR_VN_5") (pintype "input"))
    )
    (net (code "71") (name "unconnected-(IC3-LV-Pad6)") (class "Default")
      (node (ref "IC3") (pin "6") (pinfunction "LV_6") (pintype "passive"))
    )
    (net (code "72") (name "unconnected-(IC3-NC-Pad1)") (class "Default")
      (node (ref "IC3") (pin "1") (pinfunction "NC_1") (pintype "no_connect"))
    )
    (net (code "73") (name "unconnected-(IC3-OSC-Pad7)") (class "Default")
      (node (ref "IC3") (pin "7") (pinfunction "OSC_7") (pintype "output"))
    )
    (net (code "74") (name "unconnected-(IC5-TEMP-Pad1)") (class "Default")
      (node (ref "IC5") (pin "1") (pinfunction "TEMP_1") (pintype "bidirectional"))
    )
    (net (code "75") (name "unconnected-(U$1-GND1-PadP$1)") (class "Default")
      (node (ref "U$1") (pin "P$1") (pinfunction "GND1_P$1") (pintype "bidirectional"))
    )
    (net (code "76") (name "unconnected-(U$1-GND2-PadP$2)") (class "Default")
      (node (ref "U$1") (pin "P$2") (pinfunction "GND2_P$2") (pintype "bidirectional"))
    )
    (net (code "77") (name "unconnected-(U$1-Pad2)") (class "Default")
      (node (ref "U$1") (pin "2") (pinfunction "2_2") (pintype "input"))
    )
    (net (code "78") (name "unconnected-(U$1-Pad3)") (class "Default")
      (node (ref "U$1") (pin "3") (pinfunction "3_3") (pintype "input"))
    )
    (net (code "79") (name "unconnected-(U$1-Pad4)") (class "Default")
      (node (ref "U$1") (pin "4") (pinfunction "4_4") (pintype "input"))
    )
    (net (code "80") (name "unconnected-(U3-IO2-Pad24)") (class "Default")
      (node (ref "U3") (pin "24") (pinfunction "IO2_24") (pintype "bidirectional"))
    )
    (net (code "81") (name "unconnected-(U3-IO12-Pad14)") (class "Default")
      (node (ref "U3") (pin "14") (pinfunction "IO12_14") (pintype "bidirectional"))
    )
    (net (code "82") (name "unconnected-(U3-IO26-Pad11)") (class "Default")
      (node (ref "U3") (pin "11") (pinfunction "IO26_11") (pintype "bidirectional"))
    )
    (net (code "83") (name "unconnected-(U3-SCL{slash}CLK-Pad20)") (class "Default")
      (node (ref "U3") (pin "20") (pinfunction "SCL/CLK_20") (pintype "bidirectional"))
    )
    (net (code "84") (name "unconnected-(U3-SCS{slash}CMD-Pad19)") (class "Default")
      (node (ref "U3") (pin "19") (pinfunction "SCS/CMD_19") (pintype "bidirectional"))
    )
    (net (code "85") (name "unconnected-(U3-SDI{slash}SD1-Pad22)") (class "Default")
      (node (ref "U3") (pin "22") (pinfunction "SDI/SD1_22") (pintype "bidirectional"))
    )
    (net (code "86") (name "unconnected-(U3-SDO{slash}SD0-Pad21)") (class "Default")
      (node (ref "U3") (pin "21") (pinfunction "SDO/SD0_21") (pintype "bidirectional"))
    )
    (net (code "87") (name "unconnected-(U3-SHD{slash}SD2-Pad17)") (class "Default")
      (node (ref "U3") (pin "17") (pinfunction "SHD/SD2_17") (pintype "bidirectional"))
    )
    (net (code "88") (name "unconnected-(U3-SWP{slash}SD3-Pad18)") (class "Default")
      (node (ref "U3") (pin "18") (pinfunction "SWP/SD3_18") (pintype "bidirectional"))
    )
  )
)
